# Sheet6.net
KiCad netlist of a schematic drawn in Altium Designer
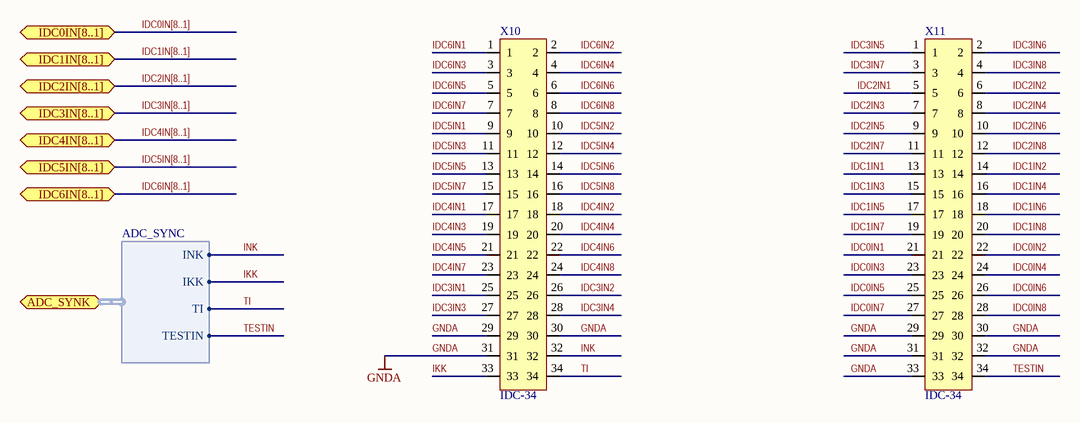
[diagram p0: Sheet6.SchDoc]

(export (version "E")
  (design (tool "Eeschema 10.0.6"))
  (components
    (comp (ref "X10")
      (value "IDC-34")
      (footprint "PLD-34")
      (description "PLD-34 or IDC 34")
      (libsource (lib "ADClib") (part "IDC34"))
    )
    (comp (ref "X11")
      (value "IDC-34")
      (footprint "PLD-34")
      (description "PLD-34 or IDC 34")
      (libsource (lib "ADClib") (part "IDC34"))
    )
  )
  (nets
    (net (code "2") (name "/IDC0IN1") (class "Default")
      (node (ref "X11") (pin "21") (pinfunction "21_21") (pintype "passive"))
    )
    (net (code "3") (name "/IDC0IN2") (class "Default")
      (node (ref "X11") (pin "22") (pinfunction "22_22") (pintype "passive"))
    )
    (net (code "4") (name "/IDC0IN3") (class "Default")
      (node (ref "X11") (pin "23") (pinfunction "23_23") (pintype "passive"))
    )
    (net (code "5") (name "/IDC0IN4") (class "Default")
      (node (ref "X11") (pin "24") (pinfunction "24_24") (pintype "passive"))
    )
    (net (code "6") (name "/IDC0IN5") (class "Default")
      (node (ref "X11") (pin "25") (pinfunction "25_25") (pintype "passive"))
    )
    (net (code "7") (name "/IDC0IN6") (class "Default")
      (node (ref "X11") (pin "26") (pinfunction "26_26") (pintype "passive"))
    )
    (net (code "8") (name "/IDC0IN7") (class "Default")
      (node (ref "X11") (pin "27") (pinfunction "27_27") (pintype "passive"))
    )
    (net (code "9") (name "/IDC0IN8") (class "Default")
      (node (ref "X11") (pin "28") (pinfunction "28_28") (pintype "passive"))
    )
    (net (code "11") (name "/IDC1IN1") (class "Default")
      (node (ref "X11") (pin "13") (pinfunction "13_13") (pintype "passive"))
    )
    (net (code "12") (name "/IDC1IN2") (class "Default")
      (node (ref "X11") (pin "14") (pinfunction "14_14") (pintype "passive"))
    )
    (net (code "13") (name "/IDC1IN3") (class "Default")
      (node (ref "X11") (pin "15") (pinfunction "15_15") (pintype "passive"))
    )
    (net (code "14") (name "/IDC1IN4") (class "Default")
      (node (ref "X11") (pin "16") (pinfunction "16_16") (pintype "passive"))
    )
    (net (code "15") (name "/IDC1IN5") (class "Default")
      (node (ref "X11") (pin "17") (pinfunction "17_17") (pintype "passive"))
    )
    (net (code "16") (name "/IDC1IN6") (class "Default")
      (node (ref "X11") (pin "18") (pinfunction "18_18") (pintype "passive"))
    )
    (net (code "17") (name "/IDC1IN7") (class "Default")
      (node (ref "X11") (pin "19") (pinfunction "19_19") (pintype "passive"))
    )
    (net (code "18") (name "/IDC1IN8") (class "Default")
      (node (ref "X11") (pin "20") (pinfunction "20_20") (pintype "passive"))
    )
    (net (code "20") (name "/IDC2IN1") (class "Default")
      (node (ref "X11") (pin "5") (pinfunction "5_5") (pintype "passive"))
    )
    (net (code "21") (name "/IDC2IN2") (class "Default")
      (node (ref "X11") (pin "6") (pinfunction "6_6") (pintype "passive"))
    )
    (net (code "22") (name "/IDC2IN3") (class "Default")
      (node (ref "X11") (pin "7") (pinfunction "7_7") (pintype "passive"))
    )
    (net (code "23") (name "/IDC2IN4") (class "Default")
      (node (ref "X11") (pin "8") (pinfunction "8_8") (pintype "passive"))
    )
    (net (code "24") (name "/IDC2IN5") (class "Default")
      (node (ref "X11") (pin "9") (pinfunction "9_9") (pintype "passive"))
    )
    (net (code "25") (name "/IDC2IN6") (class "Default")
      (node (ref "X11") (pin "10") (pinfunction "10_10") (pintype "passive"))
    )
    (net (code "26") (name "/IDC2IN7") (class "Default")
      (node (ref "X11") (pin "11") (pinfunction "11_11") (pintype "passive"))
    )
    (net (code "27") (name "/IDC2IN8") (class "Default")
      (node (ref "X11") (pin "12") (pinfunction "12_12") (pintype "passive"))
    )
    (net (code "29") (name "/IDC3IN1") (class "Default")
      (node (ref "X10") (pin "25") (pinfunction "25_25") (pintype "passive"))
    )
    (net (code "30") (name "/IDC3IN2") (class "Default")
      (node (ref "X10") (pin "26") (pinfunction "26_26") (pintype "passive"))
    )
    (net (code "31") (name "/IDC3IN3") (class "Default")
      (node (ref "X10") (pin "27") (pinfunction "27_27") (pintype "passive"))
    )
    (net (code "32") (name "/IDC3IN4") (class "Default")
      (node (ref "X10") (pin "28") (pinfunction "28_28") (pintype "passive"))
    )
    (net (code "33") (name "/IDC3IN5") (class "Default")
      (node (ref "X11") (pin "1") (pinfunction "1_1") (pintype "passive"))
    )
    (net (code "34") (name "/IDC3IN6") (class "Default")
      (node (ref "X11") (pin "2") (pinfunction "2_2") (pintype "passive"))
    )
    (net (code "35") (name "/IDC3IN7") (class "Default")
      (node (ref "X11") (pin "3") (pinfunction "3_3") (pintype "passive"))
    )
    (net (code "36") (name "/IDC3IN8") (class "Default")
      (node (ref "X11") (pin "4") (pinfunction "4_4") (pintype "passive"))
    )
    (net (code "38") (name "/IDC4IN1") (class "Default")
      (node (ref "X10") (pin "17") (pinfunction "17_17") (pintype "passive"))
    )
    (net (code "39") (name "/IDC4IN2") (class "Default")
      (node (ref "X10") (pin "18") (pinfunction "18_18") (pintype "passive"))
    )
    (net (code "40") (name "/IDC4IN3") (class "Default")
      (node (ref "X10") (pin "19") (pinfunction "19_19") (pintype "passive"))
    )
    (net (code "41") (name "/IDC4IN4") (class "Default")
      (node (ref "X10") (pin "20") (pinfunction "20_20") (pintype "passive"))
    )
    (net (code "42") (name "/IDC4IN5") (class "Default")
      (node (ref "X10") (pin "21") (pinfunction "21_21") (pintype "passive"))
    )
    (net (code "43") (name "/IDC4IN6") (class "Default")
      (node (ref "X10") (pin "22") (pinfunction "22_22") (pintype "passive"))
    )
    (net (code "44") (name "/IDC4IN7") (class "Default")
      (node (ref "X10") (pin "23") (pinfunction "23_23") (pintype "passive"))
    )
    (net (code "45") (name "/IDC4IN8") (class "Default")
      (node (ref "X10") (pin "24") (pinfunction "24_24") (pintype "passive"))
    )
    (net (code "47") (name "/IDC5IN1") (class "Default")
      (node (ref "X10") (pin "9") (pinfunction "9_9") (pintype "passive"))
    )
    (net (code "48") (name "/IDC5IN2") (class "Default")
      (node (ref "X10") (pin "10") (pinfunction "10_10") (pintype "passive"))
    )
    (net (code "49") (name "/IDC5IN3") (class "Default")
      (node (ref "X10") (pin "11") (pinfunction "11_11") (pintype "passive"))
    )
    (net (code "50") (name "/IDC5IN4") (class "Default")
      (node (ref "X10") (pin "12") (pinfunction "12_12") (pintype "passive"))
    )
    (net (code "51") (name "/IDC5IN5") (class "Default")
      (node (ref "X10") (pin "13") (pinfunction "13_13") (pintype "passive"))
    )
    (net (code "52") (name "/IDC5IN6") (class "Default")
      (node (ref "X10") (pin "14") (pinfunction "14_14") (pintype "passive"))
    )
    (net (code "53") (name "/IDC5IN7") (class "Default")
      (node (ref "X10") (pin "15") (pinfunction "15_15") (pintype "passive"))
    )
    (net (code "54") (name "/IDC5IN8") (class "Default")
      (node (ref "X10") (pin "16") (pinfunction "16_16") (pintype "passive"))
    )
    (net (code "56") (name "/IDC6IN1") (class "Default")
      (node (ref "X10") (pin "1") (pinfunction "1_1") (pintype "passive"))
    )
    (net (code "57") (name "/IDC6IN2") (class "Default")
      (node (ref "X10") (pin "2") (pinfunction "2_2") (pintype "passive"))
    )
    (net (code "58") (name "/IDC6IN3") (class "Default")
      (node (ref "X10") (pin "3") (pinfunction "3_3") (pintype "passive"))
    )
    (net (code "59") (name "/IDC6IN4") (class "Default")
      (node (ref "X10") (pin "4") (pinfunction "4_4") (pintype "passive"))
    )
    (net (code "60") (name "/IDC6IN5") (class "Default")
      (node (ref "X10") (pin "5") (pinfunction "5_5") (pintype "passive"))
    )
    (net (code "61") (name "/IDC6IN6") (class "Default")
      (node (ref "X10") (pin "6") (pinfunction "6_6") (pintype "passive"))
    )
    (net (code "62") (name "/IDC6IN7") (class "Default")
      (node (ref "X10") (pin "7") (pinfunction "7_7") (pintype "passive"))
    )
    (net (code "63") (name "/IDC6IN8") (class "Default")
      (node (ref "X10") (pin "8") (pinfunction "8_8") (pintype "passive"))
    )
    (net (code "65") (name "/IKK") (class "Default")
      (node (ref "X10") (pin "33") (pinfunction "33_33") (pintype "passive"))
    )
    (net (code "66") (name "/INK") (class "Default")
      (node (ref "X10") (pin "32") (pinfunction "32_32") (pintype "passive"))
    )
    (net (code "67") (name "/TESTIN") (class "Default")
      (node (ref "X11") (pin "34") (pinfunction "34_34") (pintype "passive"))
    )
    (net (code "68") (name "/TI") (class "Default")
      (node (ref "X10") (pin "34") (pinfunction "34_34") (pintype "passive"))
    )
    (net (code "70") (name "GNDA") (class "Default")
      (node (ref "X10") (pin "29") (pinfunction "29_29") (pintype "passive"))
      (node (ref "X10") (pin "30") (pinfunction "30_30") (pintype "passive"))
      (node (ref "X10") (pin "31") (pinfunction "31_31") (pintype "passive"))
      (node (ref "X11") (pin "29") (pinfunction "29_29") (pintype "passive"))
      (node (ref "X11") (pin "30") (pinfunction "30_30") (pintype "passive"))
      (node (ref "X11") (pin "31") (pinfunction "31_31") (pintype "passive"))
      (node (ref "X11") (pin "32") (pinfunction "32_32") (pintype "passive"))
      (node (ref "X11") (pin "33") (pinfunction "33_33") (pintype "passive"))
    )
  )
)
